# scheme.net
KiCad netlist of a schematic drawn in EAGLE
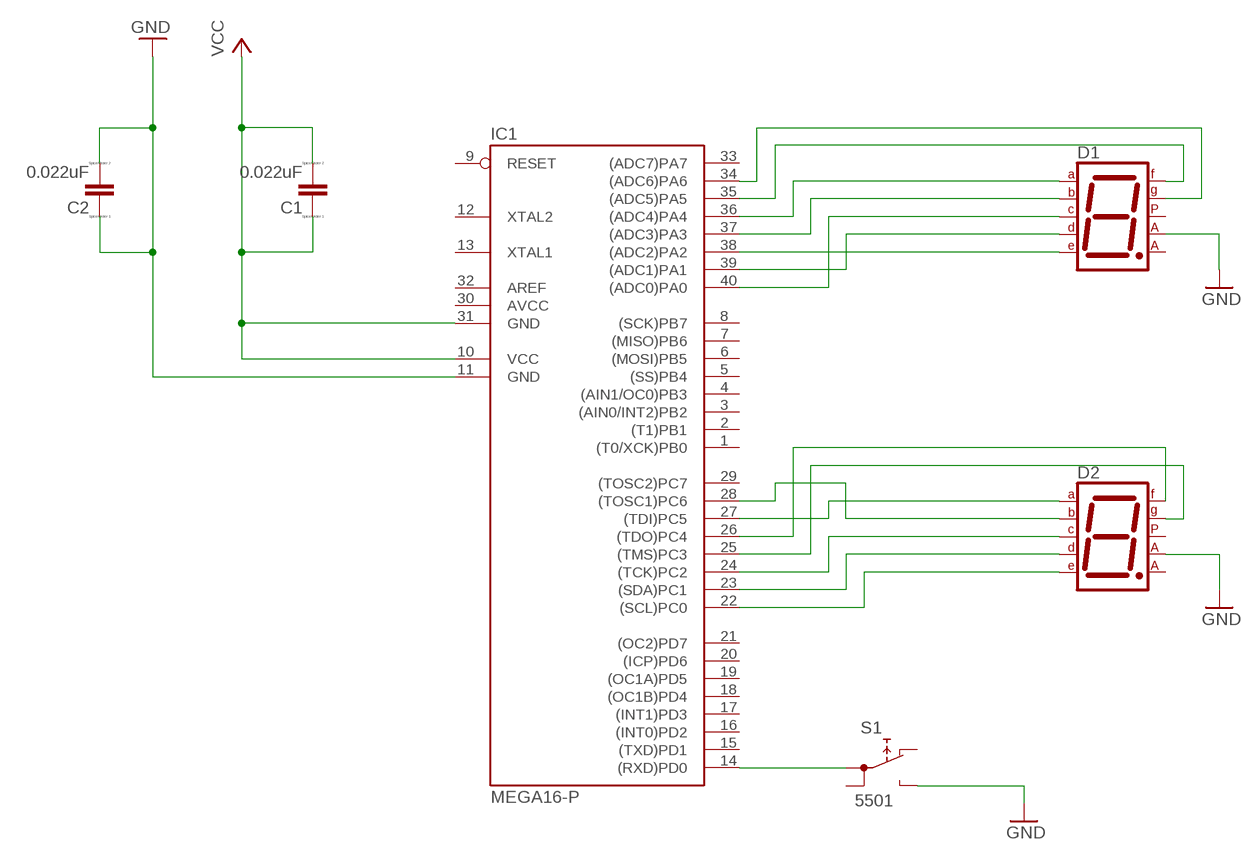
[diagram p0: schematic, sheet 1]

(export (version "E")
  (design (tool "Eeschema 10.0.6"))
  (components
    (comp (ref "C1")
      (value "0.022uF")
      (footprint "eagle-import:C0805")
      (libsource (lib "eagle-import") (part "C"))
    )
    (comp (ref "C2")
      (value "0.022uF")
      (footprint "eagle-import:C0805")
      (libsource (lib "eagle-import") (part "C"))
    )
    (comp (ref "D1")
      (value "7SEG-CA")
      (footprint "eagle-import:7SEG-13")
      (libsource (lib "eagle-import") (part "7SEG-CA"))
    )
    (comp (ref "D2")
      (value "7SEG-CA")
      (footprint "eagle-import:7SEG-13")
      (libsource (lib "eagle-import") (part "7SEG-CA"))
    )
    (comp (ref "IC1")
      (value "MEGA16-P")
      (footprint "eagle-import:DIL40")
      (fields (field (name "MPN") "ATMEGA16-16PU"))
      (libsource (lib "eagle-import") (part "MEGA16-P"))
    )
    (comp (ref "S1")
      (value "5501")
      (footprint "eagle-import:5501")
      (libsource (lib "eagle-import") (part "55?01"))
    )
  )
  (nets
    (net (code "1") (name "/AVCC") (class "Default")
      (node (ref "IC1") (pin "30") (pinfunction "AVCC_30") (pintype "power_in"))
    )
    (net (code "2") (name "GND") (class "Default")
      (node (ref "C2") (pin "1") (pinfunction "1_1") (pintype "passive"))
      (node (ref "C2") (pin "2") (pinfunction "2_2") (pintype "passive"))
      (node (ref "D1") (pin "3") (pinfunction "CA1_3") (pintype "passive"))
      (node (ref "D2") (pin "3") (pinfunction "CA1_3") (pintype "passive"))
      (node (ref "IC1") (pin "11") (pinfunction "GND_11") (pintype "power_in"))
      (node (ref "S1") (pin "NO") (pinfunction "NO_NO") (pintype "passive"))
    )
    (net (code "3") (name "Net-(D1-A)") (class "Default")
      (node (ref "D1") (pin "7") (pinfunction "A_7") (pintype "passive"))
      (node (ref "IC1") (pin "36") (pinfunction "(ADC4)PA4_36") (pintype "bidirectional"))
    )
    (net (code "4") (name "Net-(D1-B)") (class "Default")
      (node (ref "D1") (pin "6") (pinfunction "B_6") (pintype "passive"))
      (node (ref "IC1") (pin "37") (pinfunction "(ADC3)PA3_37") (pintype "bidirectional"))
    )
    (net (code "5") (name "Net-(D1-C)") (class "Default")
      (node (ref "D1") (pin "4") (pinfunction "C_4") (pintype "passive"))
      (node (ref "IC1") (pin "40") (pinfunction "(ADC0)PA0_40") (pintype "bidirectional"))
    )
    (net (code "6") (name "Net-(D1-D)") (class "Default")
      (node (ref "D1") (pin "2") (pinfunction "D_2") (pintype "passive"))
      (node (ref "IC1") (pin "39") (pinfunction "(ADC1)PA1_39") (pintype "bidirectional"))
    )
    (net (code "7") (name "Net-(D1-E)") (class "Default")
      (node (ref "D1") (pin "1") (pinfunction "E_1") (pintype "passive"))
      (node (ref "IC1") (pin "38") (pinfunction "(ADC2)PA2_38") (pintype "bidirectional"))
    )
    (net (code "8") (name "Net-(D1-F)") (class "Default")
      (node (ref "D1") (pin "9") (pinfunction "F_9") (pintype "passive"))
      (node (ref "IC1") (pin "35") (pinfunction "(ADC5)PA5_35") (pintype "bidirectional"))
    )
    (net (code "9") (name "Net-(D1-G)") (class "Default")
      (node (ref "D1") (pin "10") (pinfunction "G_10") (pintype "passive"))
      (node (ref "IC1") (pin "34") (pinfunction "(ADC6)PA6_34") (pintype "bidirectional"))
    )
    (net (code "10") (name "Net-(D2-A)") (class "Default")
      (node (ref "D2") (pin "7") (pinfunction "A_7") (pintype "passive"))
      (node (ref "IC1") (pin "27") (pinfunction "(TDI)PC5_27") (pintype "bidirectional"))
    )
    (net (code "11") (name "Net-(D2-B)") (class "Default")
      (node (ref "D2") (pin "6") (pinfunction "B_6") (pintype "passive"))
      (node (ref "IC1") (pin "28") (pinfunction "(TOSC1)PC6_28") (pintype "bidirectional"))
    )
    (net (code "12") (name "Net-(D2-C)") (class "Default")
      (node (ref "D2") (pin "4") (pinfunction "C_4") (pintype "passive"))
      (node (ref "IC1") (pin "24") (pinfunction "(TCK)PC2_24") (pintype "bidirectional"))
    )
    (net (code "13") (name "Net-(D2-D)") (class "Default")
      (node (ref "D2") (pin "2") (pinfunction "D_2") (pintype "passive"))
      (node (ref "IC1") (pin "23") (pinfunction "(SDA)PC1_23") (pintype "bidirectional"))
    )
    (net (code "14") (name "Net-(D2-E)") (class "Default")
      (node (ref "D2") (pin "1") (pinfunction "E_1") (pintype "passive"))
      (node (ref "IC1") (pin "22") (pinfunction "(SCL)PC0_22") (pintype "bidirectional"))
    )
    (net (code "15") (name "Net-(D2-F)") (class "Default")
      (node (ref "D2") (pin "9") (pinfunction "F_9") (pintype "passive"))
      (node (ref "IC1") (pin "26") (pinfunction "(TDO)PC4_26") (pintype "bidirectional"))
    )
    (net (code "16") (name "Net-(D2-G)") (class "Default")
      (node (ref "D2") (pin "10") (pinfunction "G_10") (pintype "passive"))
      (node (ref "IC1") (pin "25") (pinfunction "(TMS)PC3_25") (pintype "bidirectional"))
    )
    (net (code "17") (name "Net-(IC1-(RXD)PD0)") (class "Default")
      (node (ref "IC1") (pin "14") (pinfunction "(RXD)PD0_14") (pintype "bidirectional"))
      (node (ref "S1") (pin "1A") (pinfunction "1A_1A") (pintype "passive"))
    )
    (net (code "18") (name "VCC") (class "Default")
      (node (ref "C1") (pin "1") (pinfunction "1_1") (pintype "passive"))
      (node (ref "C1") (pin "2") (pinfunction "2_2") (pintype "passive"))
      (node (ref "IC1") (pin "10") (pinfunction "VCC_10") (pintype "power_in"))
      (node (ref "IC1") (pin "31") (pinfunction "GND_31") (pintype "power_in"))
    )
    (net (code "19") (name "unconnected-(D1-CA2-Pad8)") (class "Default")
      (node (ref "D1") (pin "8") (pinfunction "CA2_8") (pintype "passive"))
    )
    (net (code "20") (name "unconnected-(D1-DP-Pad5)") (class "Default")
      (node (ref "D1") (pin "5") (pinfunction "DP_5") (pintype "passive"))
    )
    (net (code "21") (name "unconnected-(D2-CA2-Pad8)") (class "Default")
      (node (ref "D2") (pin "8") (pinfunction "CA2_8") (pintype "passive"))
    )
    (net (code "22") (name "unconnected-(D2-DP-Pad5)") (class "Default")
      (node (ref "D2") (pin "5") (pinfunction "DP_5") (pintype "passive"))
    )
    (net (code "23") (name "unconnected-(IC1-(ADC7)PA7-Pad33)") (class "Default")
      (node (ref "IC1") (pin "33") (pinfunction "(ADC7)PA7_33") (pintype "bidirectional"))
    )
    (net (code "24") (name "unconnected-(IC1-(AIN0{slash}INT2)PB2-Pad3)") (class "Default")
      (node (ref "IC1") (pin "3") (pinfunction "(AIN0/INT2)PB2_3") (pintype "bidirectional"))
    )
    (net (code "25") (name "unconnected-(IC1-(AIN1{slash}OC0)PB3-Pad4)") (class "Default")
      (node (ref "IC1") (pin "4") (pinfunction "(AIN1/OC0)PB3_4") (pintype "bidirectional"))
    )
    (net (code "26") (name "unconnected-(IC1-(ICP)PD6-Pad20)") (class "Default")
      (node (ref "IC1") (pin "20") (pinfunction "(ICP)PD6_20") (pintype "bidirectional"))
    )
    (net (code "27") (name "unconnected-(IC1-(INT0)PD2-Pad16)") (class "Default")
      (node (ref "IC1") (pin "16") (pinfunction "(INT0)PD2_16") (pintype "bidirectional"))
    )
    (net (code "28") (name "unconnected-(IC1-(INT1)PD3-Pad17)") (class "Default")
      (node (ref "IC1") (pin "17") (pinfunction "(INT1)PD3_17") (pintype "bidirectional"))
    )
    (net (code "29") (name "unconnected-(IC1-(MISO)PB6-Pad7)") (class "Default")
      (node (ref "IC1") (pin "7") (pinfunction "(MISO)PB6_7") (pintype "bidirectional"))
    )
    (net (code "30") (name "unconnected-(IC1-(MOSI)PB5-Pad6)") (class "Default")
      (node (ref "IC1") (pin "6") (pinfunction "(MOSI)PB5_6") (pintype "bidirectional"))
    )
    (net (code "31") (name "unconnected-(IC1-(OC1A)PD5-Pad19)") (class "Default")
      (node (ref "IC1") (pin "19") (pinfunction "(OC1A)PD5_19") (pintype "bidirectional"))
    )
    (net (code "32") (name "unconnected-(IC1-(OC1B)PD4-Pad18)") (class "Default")
      (node (ref "IC1") (pin "18") (pinfunction "(OC1B)PD4_18") (pintype "bidirectional"))
    )
    (net (code "33") (name "unconnected-(IC1-(OC2)PD7-Pad21)") (class "Default")
      (node (ref "IC1") (pin "21") (pinfunction "(OC2)PD7_21") (pintype "bidirectional"))
    )
    (net (code "34") (name "unconnected-(IC1-(SCK)PB7-Pad8)") (class "Default")
      (node (ref "IC1") (pin "8") (pinfunction "(SCK)PB7_8") (pintype "bidirectional"))
    )
    (net (code "35") (name "unconnected-(IC1-(SS)PB4-Pad5)") (class "Default")
      (node (ref "IC1") (pin "5") (pinfunction "(SS)PB4_5") (pintype "bidirectional"))
    )
    (net (code "36") (name "unconnected-(IC1-(T0{slash}XCK)PB0-Pad1)") (class "Default")
      (node (ref "IC1") (pin "1") (pinfunction "(T0/XCK)PB0_1") (pintype "bidirectional"))
    )
    (net (code "37") (name "unconnected-(IC1-(T1)PB1-Pad2)") (class "Default")
      (node (ref "IC1") (pin "2") (pinfunction "(T1)PB1_2") (pintype "bidirectional"))
    )
    (net (code "38") (name "unconnected-(IC1-(TOSC2)PC7-Pad29)") (class "Default")
      (node (ref "IC1") (pin "29") (pinfunction "(TOSC2)PC7_29") (pintype "bidirectional"))
    )
    (net (code "39") (name "unconnected-(IC1-(TXD)PD1-Pad15)") (class "Default")
      (node (ref "IC1") (pin "15") (pinfunction "(TXD)PD1_15") (pintype "bidirectional"))
    )
    (net (code "40") (name "unconnected-(IC1-AREF-Pad32)") (class "Default")
      (node (ref "IC1") (pin "32") (pinfunction "AREF_32") (pintype "passive"))
    )
    (net (code "41") (name "unconnected-(IC1-RESET-Pad9)") (class "Default")
      (node (ref "IC1") (pin "9") (pinfunction "RESET_9") (pintype "input"))
    )
    (net (code "42") (name "unconnected-(IC1-XTAL1-Pad13)") (class "Default")
      (node (ref "IC1") (pin "13") (pinfunction "XTAL1_13") (pintype "bidirectional"))
    )
    (net (code "43") (name "unconnected-(IC1-XTAL2-Pad12)") (class "Default")
      (node (ref "IC1") (pin "12") (pinfunction "XTAL2_12") (pintype "bidirectional"))
    )
    (net (code "44") (name "unconnected-(S1-Pad1B)") (class "Default")
      (node (ref "S1") (pin "1B") (pinfunction "1B_1B") (pintype "passive"))
    )
    (net (code "45") (name "unconnected-(S1-PadNC)") (class "Default")
      (node (ref "S1") (pin "NC") (pinfunction "NC_NC") (pintype "passive"))
    )
  )
)
